# LoRa.net
KiCad netlist of a schematic drawn in Altium Designer
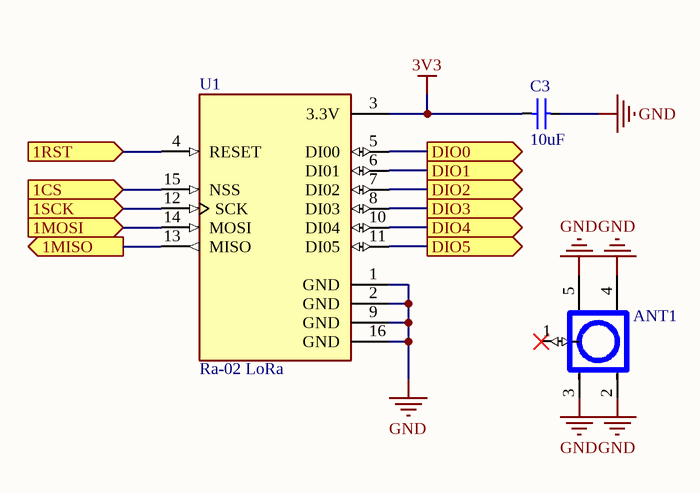
[diagram p0: LoRa.SchDoc]

(export (version "E")
  (design (tool "Eeschema 10.0.6"))
  (components
    (comp (ref "ANT1")
      (value "anten")
      (footprint "SMA-RA")
      (description "Anten 5 pins")
      (libsource (lib "My Library") (part "anten"))
    )
    (comp (ref "C3")
      (value "10uF")
      (footprint "CAP_0805")
      (description "Capacitor")
      (fields (field (name "PUBLISHER") "Altium Limited"))
      (libsource (lib "My Library") (part "CapSMD"))
    )
    (comp (ref "U1")
      (value "Ra-02 LoRa")
      (footprint "Ra-02")
      (description "LoRa Module Ra-02")
      (libsource (lib "Ven_lib") (part "Ra-02 LoRa"))
    )
  )
  (nets
    (net (code "1") (name "/1CS") (class "Default")
      (node (ref "U1") (pin "15") (pinfunction "NSS_15") (pintype "input"))
    )
    (net (code "2") (name "/1MISO") (class "Default")
      (node (ref "U1") (pin "13") (pinfunction "MISO_13") (pintype "output"))
    )
    (net (code "3") (name "/1MOSI") (class "Default")
      (node (ref "U1") (pin "14") (pinfunction "MOSI_14") (pintype "input"))
    )
    (net (code "4") (name "/1RST") (class "Default")
      (node (ref "U1") (pin "4") (pinfunction "RESET_4") (pintype "input"))
    )
    (net (code "5") (name "/1SCK") (class "Default")
      (node (ref "U1") (pin "12") (pinfunction "SCK_12") (pintype "input"))
    )
    (net (code "6") (name "/DIO0") (class "Default")
      (node (ref "U1") (pin "5") (pinfunction "DI00_5") (pintype "bidirectional"))
    )
    (net (code "7") (name "/DIO1") (class "Default")
      (node (ref "U1") (pin "6") (pinfunction "DI01_6") (pintype "bidirectional"))
    )
    (net (code "8") (name "/DIO2") (class "Default")
      (node (ref "U1") (pin "7") (pinfunction "DI02_7") (pintype "bidirectional"))
    )
    (net (code "9") (name "/DIO3") (class "Default")
      (node (ref "U1") (pin "8") (pinfunction "DI03_8") (pintype "bidirectional"))
    )
    (net (code "10") (name "/DIO4") (class "Default")
      (node (ref "U1") (pin "10") (pinfunction "DI04_10") (pintype "bidirectional"))
    )
    (net (code "11") (name "/DIO5") (class "Default")
      (node (ref "U1") (pin "11") (pinfunction "DI05_11") (pintype "bidirectional"))
    )
    (net (code "12") (name "3V3") (class "Default")
      (node (ref "C3") (pin "2") (pinfunction "2_2") (pintype "passive"))
      (node (ref "U1") (pin "3") (pinfunction "3.3V_3") (pintype "power_in"))
    )
    (net (code "13") (name "GND") (class "Default")
      (node (ref "ANT1") (pin "2") (pintype "passive"))
      (node (ref "ANT1") (pin "3") (pintype "passive"))
      (node (ref "ANT1") (pin "4") (pintype "passive"))
      (node (ref "ANT1") (pin "5") (pintype "passive"))
      (node (ref "C3") (pin "1") (pinfunction "1_1") (pintype "passive"))
      (node (ref "U1") (pin "1") (pinfunction "GND_1") (pintype "power_in"))
      (node (ref "U1") (pin "16") (pinfunction "GND_16") (pintype "power_in"))
      (node (ref "U1") (pin "2") (pinfunction "GND_2") (pintype "power_in"))
      (node (ref "U1") (pin "9") (pinfunction "GND_9") (pintype "power_in"))
    )
    (net (code "14") (name "unconnected-(ANT1-Pad1)") (class "Default")
      (node (ref "ANT1") (pin "1") (pintype "bidirectional+no_connect"))
    )
  )
)
